# MUX_Block.net
KiCad netlist of a schematic drawn in Altium Designer
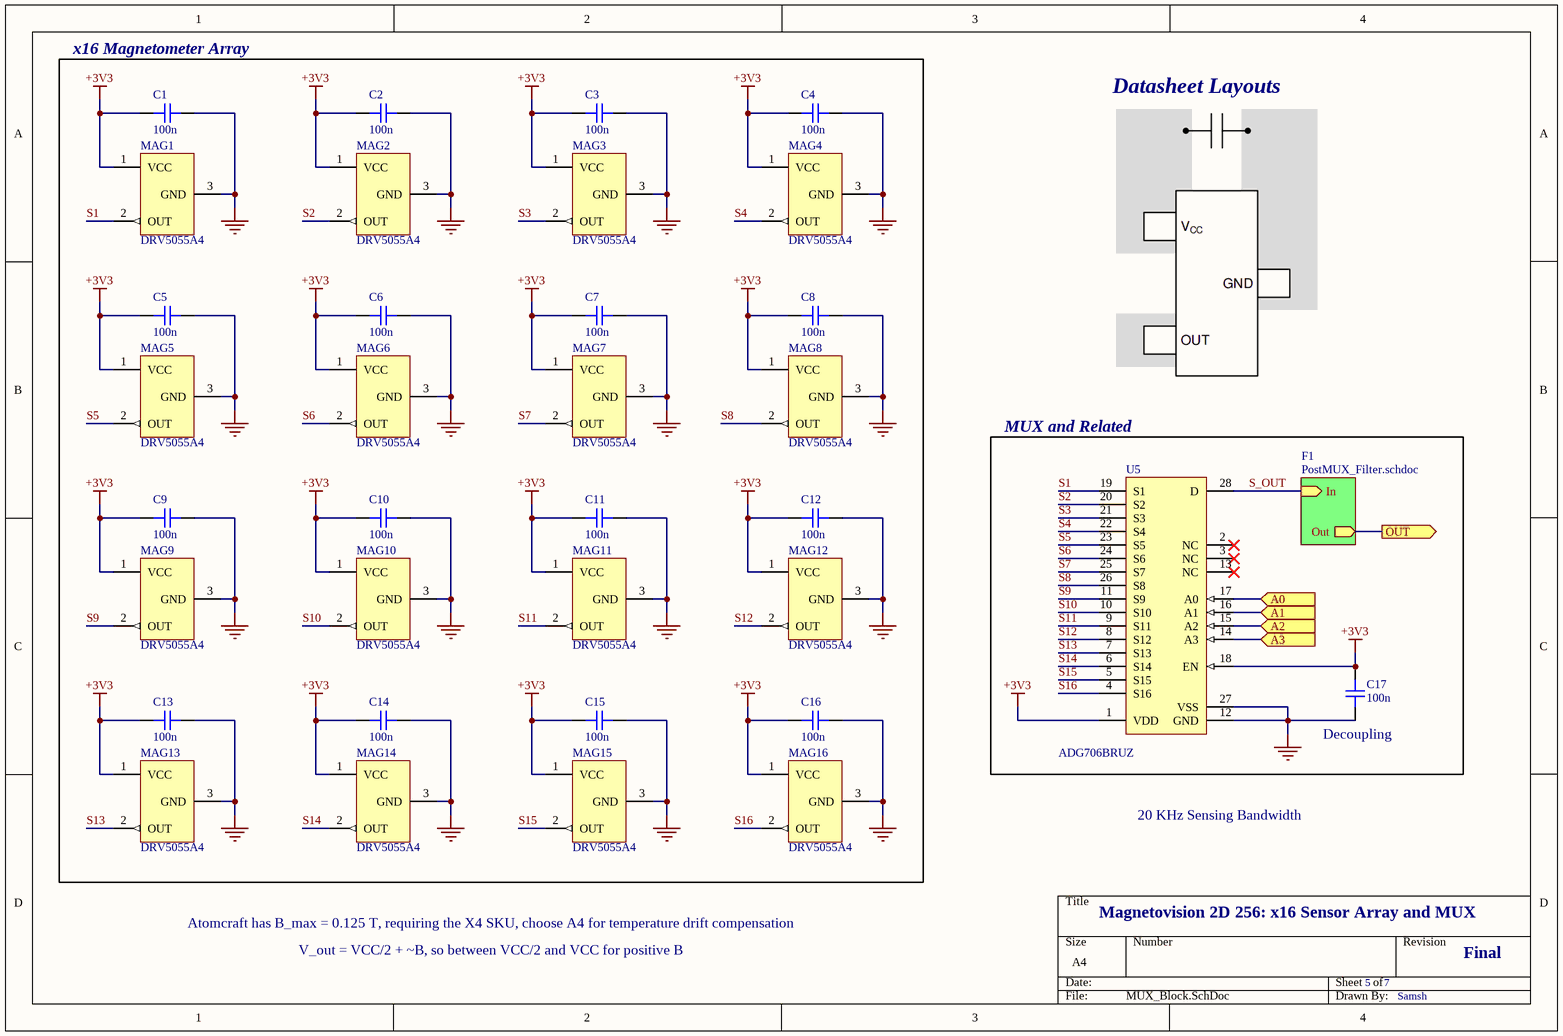
[diagram p0: MUX_Block.SchDoc]

(export (version "E")
  (design (tool "Eeschema 10.0.6"))
  (components
    (comp (ref "C1")
      (value "100n")
      (footprint "CAP_0603")
      (description "Capacitor SMD 0603")
      (fields (field (name "SOURCE") "Schematic-Lib-PhilsLab.SchLib"))
      (libsource (lib "Samsh Nanoelectronics") (part "CAP_EL_NP_5MM"))
    )
    (comp (ref "C2")
      (value "100n")
      (footprint "CAP_0603")
      (description "Capacitor SMD 0603")
      (fields (field (name "SOURCE") "Schematic-Lib-PhilsLab.SchLib"))
      (libsource (lib "Samsh Nanoelectronics") (part "CAP_EL_NP_5MM"))
    )
    (comp (ref "C3")
      (value "100n")
      (footprint "CAP_0603")
      (description "Capacitor SMD 0603")
      (fields (field (name "SOURCE") "Schematic-Lib-PhilsLab.SchLib"))
      (libsource (lib "Samsh Nanoelectronics") (part "CAP_EL_NP_5MM"))
    )
    (comp (ref "C4")
      (value "100n")
      (footprint "CAP_0603")
      (description "Capacitor SMD 0603")
      (fields (field (name "SOURCE") "Schematic-Lib-PhilsLab.SchLib"))
      (libsource (lib "Samsh Nanoelectronics") (part "CAP_EL_NP_5MM"))
    )
    (comp (ref "C5")
      (value "100n")
      (footprint "CAP_0603")
      (description "Capacitor SMD 0603")
      (fields (field (name "SOURCE") "Schematic-Lib-PhilsLab.SchLib"))
      (libsource (lib "Samsh Nanoelectronics") (part "CAP_EL_NP_5MM"))
    )
    (comp (ref "C6")
      (value "100n")
      (footprint "CAP_0603")
      (description "Capacitor SMD 0603")
      (fields (field (name "SOURCE") "Schematic-Lib-PhilsLab.SchLib"))
      (libsource (lib "Samsh Nanoelectronics") (part "CAP_EL_NP_5MM"))
    )
    (comp (ref "C7")
      (value "100n")
      (footprint "CAP_0603")
      (description "Capacitor SMD 0603")
      (fields (field (name "SOURCE") "Schematic-Lib-PhilsLab.SchLib"))
      (libsource (lib "Samsh Nanoelectronics") (part "CAP_EL_NP_5MM"))
    )
    (comp (ref "C8")
      (value "100n")
      (footprint "CAP_0603")
      (description "Capacitor SMD 0603")
      (fields (field (name "SOURCE") "Schematic-Lib-PhilsLab.SchLib"))
      (libsource (lib "Samsh Nanoelectronics") (part "CAP_EL_NP_5MM"))
    )
    (comp (ref "C9")
      (value "100n")
      (footprint "CAP_0603")
      (description "Capacitor SMD 0603")
      (fields (field (name "SOURCE") "Schematic-Lib-PhilsLab.SchLib"))
      (libsource (lib "Samsh Nanoelectronics") (part "CAP_EL_NP_5MM"))
    )
    (comp (ref "C10")
      (value "100n")
      (footprint "CAP_0603")
      (description "Capacitor SMD 0603")
      (fields (field (name "SOURCE") "Schematic-Lib-PhilsLab.SchLib"))
      (libsource (lib "Samsh Nanoelectronics") (part "CAP_EL_NP_5MM"))
    )
    (comp (ref "C11")
      (value "100n")
      (footprint "CAP_0603")
      (description "Capacitor SMD 0603")
      (fields (field (name "SOURCE") "Schematic-Lib-PhilsLab.SchLib"))
      (libsource (lib "Samsh Nanoelectronics") (part "CAP_EL_NP_5MM"))
    )
    (comp (ref "C12")
      (value "100n")
      (footprint "CAP_0603")
      (description "Capacitor SMD 0603")
      (fields (field (name "SOURCE") "Schematic-Lib-PhilsLab.SchLib"))
      (libsource (lib "Samsh Nanoelectronics") (part "CAP_EL_NP_5MM"))
    )
    (comp (ref "C13")
      (value "100n")
      (footprint "CAP_0603")
      (description "Capacitor SMD 0603")
      (fields (field (name "SOURCE") "Schematic-Lib-PhilsLab.SchLib"))
      (libsource (lib "Samsh Nanoelectronics") (part "CAP_EL_NP_5MM"))
    )
    (comp (ref "C14")
      (value "100n")
      (footprint "CAP_0603")
      (description "Capacitor SMD 0603")
      (fields (field (name "SOURCE") "Schematic-Lib-PhilsLab.SchLib"))
      (libsource (lib "Samsh Nanoelectronics") (part "CAP_EL_NP_5MM"))
    )
    (comp (ref "C15")
      (value "100n")
      (footprint "CAP_0603")
      (description "Capacitor SMD 0603")
      (fields (field (name "SOURCE") "Schematic-Lib-PhilsLab.SchLib"))
      (libsource (lib "Samsh Nanoelectronics") (part "CAP_EL_NP_5MM"))
    )
    (comp (ref "C16")
      (value "100n")
      (footprint "CAP_0603")
      (description "Capacitor SMD 0603")
      (fields (field (name "SOURCE") "Schematic-Lib-PhilsLab.SchLib"))
      (libsource (lib "Samsh Nanoelectronics") (part "CAP_EL_NP_5MM"))
    )
    (comp (ref "C17")
      (value "100n")
      (footprint "CAP_0603")
      (description "Capacitor SMD 0603")
      (fields (field (name "SOURCE") "Schematic-Lib-PhilsLab.SchLib"))
      (libsource (lib "Samsh Nanoelectronics") (part "CAP_EL_NP_5MM"))
    )
    (comp (ref "MAG1")
      (value "DRV5055A4")
      (footprint "SOT100P237X112-3N")
      (libsource (lib "Samsh Nanoelectronics") (part "DRV5055A4"))
    )
    (comp (ref "MAG2")
      (value "DRV5055A4")
      (footprint "SOT100P237X112-3N")
      (libsource (lib "Samsh Nanoelectronics") (part "DRV5055A4"))
    )
    (comp (ref "MAG3")
      (value "DRV5055A4")
      (footprint "SOT100P237X112-3N")
      (libsource (lib "Samsh Nanoelectronics") (part "DRV5055A4"))
    )
    (comp (ref "MAG4")
      (value "DRV5055A4")
      (footprint "SOT100P237X112-3N")
      (libsource (lib "Samsh Nanoelectronics") (part "DRV5055A4"))
    )
    (comp (ref "MAG5")
      (value "DRV5055A4")
      (footprint "SOT100P237X112-3N")
      (libsource (lib "Samsh Nanoelectronics") (part "DRV5055A4"))
    )
    (comp (ref "MAG6")
      (value "DRV5055A4")
      (footprint "SOT100P237X112-3N")
      (libsource (lib "Samsh Nanoelectronics") (part "DRV5055A4"))
    )
    (comp (ref "MAG7")
      (value "DRV5055A4")
      (footprint "SOT100P237X112-3N")
      (libsource (lib "Samsh Nanoelectronics") (part "DRV5055A4"))
    )
    (comp (ref "MAG8")
      (value "DRV5055A4")
      (footprint "SOT100P237X112-3N")
      (libsource (lib "Samsh Nanoelectronics") (part "DRV5055A4"))
    )
    (comp (ref "MAG9")
      (value "DRV5055A4")
      (footprint "SOT100P237X112-3N")
      (libsource (lib "Samsh Nanoelectronics") (part "DRV5055A4"))
    )
    (comp (ref "MAG10")
      (value "DRV5055A4")
      (footprint "SOT100P237X112-3N")
      (libsource (lib "Samsh Nanoelectronics") (part "DRV5055A4"))
    )
    (comp (ref "MAG11")
      (value "DRV5055A4")
      (footprint "SOT100P237X112-3N")
      (libsource (lib "Samsh Nanoelectronics") (part "DRV5055A4"))
    )
    (comp (ref "MAG12")
      (value "DRV5055A4")
      (footprint "SOT100P237X112-3N")
      (libsource (lib "Samsh Nanoelectronics") (part "DRV5055A4"))
    )
    (comp (ref "MAG13")
      (value "DRV5055A4")
      (footprint "SOT100P237X112-3N")
      (libsource (lib "Samsh Nanoelectronics") (part "DRV5055A4"))
    )
    (comp (ref "MAG14")
      (value "DRV5055A4")
      (footprint "SOT100P237X112-3N")
      (libsource (lib "Samsh Nanoelectronics") (part "DRV5055A4"))
    )
    (comp (ref "MAG15")
      (value "DRV5055A4")
      (footprint "SOT100P237X112-3N")
      (libsource (lib "Samsh Nanoelectronics") (part "DRV5055A4"))
    )
    (comp (ref "MAG16")
      (value "DRV5055A4")
      (footprint "SOT100P237X112-3N")
      (libsource (lib "Samsh Nanoelectronics") (part "DRV5055A4"))
    )
    (comp (ref "U5")
      (value "ADG706BRUZ")
      (footprint "ADI-RU-28_M")
      (fields (field (name "MANUFACTURER") "Analog Devices") (field (name "PARTNUMBER") "ADG706BRUZ-REEL7"))
      (libsource (lib "Altium Content Vault") (part "ADI-ADG706-RU-28"))
    )
  )
  (nets
    (net (code "1") (name "+3V3") (class "Default")
      (node (ref "C1") (pin "1") (pinfunction "1_1") (pintype "passive"))
      (node (ref "C10") (pin "1") (pinfunction "1_1") (pintype "passive"))
      (node (ref "C11") (pin "1") (pinfunction "1_1") (pintype "passive"))
      (node (ref "C12") (pin "1") (pinfunction "1_1") (pintype "passive"))
      (node (ref "C13") (pin "1") (pinfunction "1_1") (pintype "passive"))
      (node (ref "C14") (pin "1") (pinfunction "1_1") (pintype "passive"))
      (node (ref "C15") (pin "1") (pinfunction "1_1") (pintype "passive"))
      (node (ref "C16") (pin "1") (pinfunction "1_1") (pintype "passive"))
      (node (ref "C17") (pin "2") (pinfunction "2_2") (pintype "passive"))
      (node (ref "C2") (pin "1") (pinfunction "1_1") (pintype "passive"))
      (node (ref "C3") (pin "1") (pinfunction "1_1") (pintype "passive"))
      (node (ref "C4") (pin "1") (pinfunction "1_1") (pintype "passive"))
      (node (ref "C5") (pin "1") (pinfunction "1_1") (pintype "passive"))
      (node (ref "C6") (pin "1") (pinfunction "1_1") (pintype "passive"))
      (node (ref "C7") (pin "1") (pinfunction "1_1") (pintype "passive"))
      (node (ref "C8") (pin "1") (pinfunction "1_1") (pintype "passive"))
      (node (ref "C9") (pin "1") (pinfunction "1_1") (pintype "passive"))
      (node (ref "MAG1") (pin "1") (pinfunction "VCC_1") (pintype "power_in"))
      (node (ref "MAG10") (pin "1") (pinfunction "VCC_1") (pintype "power_in"))
      (node (ref "MAG11") (pin "1") (pinfunction "VCC_1") (pintype "power_in"))
      (node (ref "MAG12") (pin "1") (pinfunction "VCC_1") (pintype "power_in"))
      (node (ref "MAG13") (pin "1") (pinfunction "VCC_1") (pintype "power_in"))
      (node (ref "MAG14") (pin "1") (pinfunction "VCC_1") (pintype "power_in"))
      (node (ref "MAG15") (pin "1") (pinfunction "VCC_1") (pintype "power_in"))
      (node (ref "MAG16") (pin "1") (pinfunction "VCC_1") (pintype "power_in"))
      (node (ref "MAG2") (pin "1") (pinfunction "VCC_1") (pintype "power_in"))
      (node (ref "MAG3") (pin "1") (pinfunction "VCC_1") (pintype "power_in"))
      (node (ref "MAG4") (pin "1") (pinfunction "VCC_1") (pintype "power_in"))
      (node (ref "MAG5") (pin "1") (pinfunction "VCC_1") (pintype "power_in"))
      (node (ref "MAG6") (pin "1") (pinfunction "VCC_1") (pintype "power_in"))
      (node (ref "MAG7") (pin "1") (pinfunction "VCC_1") (pintype "power_in"))
      (node (ref "MAG8") (pin "1") (pinfunction "VCC_1") (pintype "power_in"))
      (node (ref "MAG9") (pin "1") (pinfunction "VCC_1") (pintype "power_in"))
      (node (ref "U5") (pin "1") (pinfunction "VDD_1") (pintype "power_in"))
      (node (ref "U5") (pin "18") (pinfunction "EN_18") (pintype "input"))
    )
    (net (code "2") (name "/A0") (class "Default")
      (node (ref "U5") (pin "17") (pinfunction "A0_17") (pintype "input"))
    )
    (net (code "3") (name "/A1") (class "Default")
      (node (ref "U5") (pin "16") (pinfunction "A1_16") (pintype "input"))
    )
    (net (code "4") (name "/A2") (class "Default")
      (node (ref "U5") (pin "15") (pinfunction "A2_15") (pintype "input"))
    )
    (net (code "5") (name "/A3") (class "Default")
      (node (ref "U5") (pin "14") (pinfunction "A3_14") (pintype "input"))
    )
    (net (code "7") (name "/S1") (class "Default")
      (node (ref "MAG1") (pin "2") (pinfunction "OUT_2") (pintype "output"))
      (node (ref "U5") (pin "19") (pinfunction "S1_19") (pintype "passive"))
    )
    (net (code "8") (name "/S2") (class "Default")
      (node (ref "MAG2") (pin "2") (pinfunction "OUT_2") (pintype "output"))
      (node (ref "U5") (pin "20") (pinfunction "S2_20") (pintype "passive"))
    )
    (net (code "9") (name "/S3") (class "Default")
      (node (ref "MAG3") (pin "2") (pinfunction "OUT_2") (pintype "output"))
      (node (ref "U5") (pin "21") (pinfunction "S3_21") (pintype "passive"))
    )
    (net (code "10") (name "/S4") (class "Default")
      (node (ref "MAG4") (pin "2") (pinfunction "OUT_2") (pintype "output"))
      (node (ref "U5") (pin "22") (pinfunction "S4_22") (pintype "passive"))
    )
    (net (code "11") (name "/S5") (class "Default")
      (node (ref "MAG5") (pin "2") (pinfunction "OUT_2") (pintype "output"))
      (node (ref "U5") (pin "23") (pinfunction "S5_23") (pintype "passive"))
    )
    (net (code "12") (name "/S6") (class "Default")
      (node (ref "MAG6") (pin "2") (pinfunction "OUT_2") (pintype "output"))
      (node (ref "U5") (pin "24") (pinfunction "S6_24") (pintype "passive"))
    )
    (net (code "13") (name "/S7") (class "Default")
      (node (ref "MAG7") (pin "2") (pinfunction "OUT_2") (pintype "output"))
      (node (ref "U5") (pin "25") (pinfunction "S7_25") (pintype "passive"))
    )
    (net (code "14") (name "/S8") (class "Default")
      (node (ref "MAG8") (pin "2") (pinfunction "OUT_2") (pintype "output"))
      (node (ref "U5") (pin "26") (pinfunction "S8_26") (pintype "passive"))
    )
    (net (code "15") (name "/S9") (class "Default")
      (node (ref "MAG9") (pin "2") (pinfunction "OUT_2") (pintype "output"))
      (node (ref "U5") (pin "11") (pinfunction "S9_11") (pintype "passive"))
    )
    (net (code "16") (name "/S10") (class "Default")
      (node (ref "MAG10") (pin "2") (pinfunction "OUT_2") (pintype "output"))
      (node (ref "U5") (pin "10") (pinfunction "S10_10") (pintype "passive"))
    )
    (net (code "17") (name "/S11") (class "Default")
      (node (ref "MAG11") (pin "2") (pinfunction "OUT_2") (pintype "output"))
      (node (ref "U5") (pin "9") (pinfunction "S11_9") (pintype "passive"))
    )
    (net (code "18") (name "/S12") (class "Default")
      (node (ref "MAG12") (pin "2") (pinfunction "OUT_2") (pintype "output"))
      (node (ref "U5") (pin "8") (pinfunction "S12_8") (pintype "passive"))
    )
    (net (code "19") (name "/S13") (class "Default")
      (node (ref "MAG13") (pin "2") (pinfunction "OUT_2") (pintype "output"))
      (node (ref "U5") (pin "7") (pinfunction "S13_7") (pintype "passive"))
    )
    (net (code "20") (name "/S14") (class "Default")
      (node (ref "MAG14") (pin "2") (pinfunction "OUT_2") (pintype "output"))
      (node (ref "U5") (pin "6") (pinfunction "S14_6") (pintype "passive"))
    )
    (net (code "21") (name "/S15") (class "Default")
      (node (ref "MAG15") (pin "2") (pinfunction "OUT_2") (pintype "output"))
      (node (ref "U5") (pin "5") (pinfunction "S15_5") (pintype "passive"))
    )
    (net (code "22") (name "/S16") (class "Default")
      (node (ref "MAG16") (pin "2") (pinfunction "OUT_2") (pintype "output"))
      (node (ref "U5") (pin "4") (pinfunction "S16_4") (pintype "passive"))
    )
    (net (code "23") (name "/S_OUT") (class "Default")
      (node (ref "U5") (pin "28") (pinfunction "D_28") (pintype "passive"))
    )
    (net (code "24") (name "GND") (class "Default")
      (node (ref "C1") (pin "2") (pinfunction "2_2") (pintype "passive"))
      (node (ref "C10") (pin "2") (pinfunction "2_2") (pintype "passive"))
      (node (ref "C11") (pin "2") (pinfunction "2_2") (pintype "passive"))
      (node (ref "C12") (pin "2") (pinfunction "2_2") (pintype "passive"))
      (node (ref "C13") (pin "2") (pinfunction "2_2") (pintype "passive"))
      (node (ref "C14") (pin "2") (pinfunction "2_2") (pintype "passive"))
      (node (ref "C15") (pin "2") (pinfunction "2_2") (pintype "passive"))
      (node (ref "C16") (pin "2") (pinfunction "2_2") (pintype "passive"))
      (node (ref "C17") (pin "1") (pinfunction "1_1") (pintype "passive"))
      (node (ref "C2") (pin "2") (pinfunction "2_2") (pintype "passive"))
      (node (ref "C3") (pin "2") (pinfunction "2_2") (pintype "passive"))
      (node (ref "C4") (pin "2") (pinfunction "2_2") (pintype "passive"))
      (node (ref "C5") (pin "2") (pinfunction "2_2") (pintype "passive"))
      (node (ref "C6") (pin "2") (pinfunction "2_2") (pintype "passive"))
      (node (ref "C7") (pin "2") (pinfunction "2_2") (pintype "passive"))
      (node (ref "C8") (pin "2") (pinfunction "2_2") (pintype "passive"))
      (node (ref "C9") (pin "2") (pinfunction "2_2") (pintype "passive"))
      (node (ref "MAG1") (pin "3") (pinfunction "GND_3") (pintype "passive"))
      (node (ref "MAG10") (pin "3") (pinfunction "GND_3") (pintype "passive"))
      (node (ref "MAG11") (pin "3") (pinfunction "GND_3") (pintype "passive"))
      (node (ref "MAG12") (pin "3") (pinfunction "GND_3") (pintype "passive"))
      (node (ref "MAG13") (pin "3") (pinfunction "GND_3") (pintype "passive"))
      (node (ref "MAG14") (pin "3") (pinfunction "GND_3") (pintype "passive"))
      (node (ref "MAG15") (pin "3") (pinfunction "GND_3") (pintype "passive"))
      (node (ref "MAG16") (pin "3") (pinfunction "GND_3") (pintype "passive"))
      (node (ref "MAG2") (pin "3") (pinfunction "GND_3") (pintype "passive"))
      (node (ref "MAG3") (pin "3") (pinfunction "GND_3") (pintype "passive"))
      (node (ref "MAG4") (pin "3") (pinfunction "GND_3") (pintype "passive"))
      (node (ref "MAG5") (pin "3") (pinfunction "GND_3") (pintype "passive"))
      (node (ref "MAG6") (pin "3") (pinfunction "GND_3") (pintype "passive"))
      (node (ref "MAG7") (pin "3") (pinfunction "GND_3") (pintype "passive"))
      (node (ref "MAG8") (pin "3") (pinfunction "GND_3") (pintype "passive"))
      (node (ref "MAG9") (pin "3") (pinfunction "GND_3") (pintype "passive"))
      (node (ref "U5") (pin "12") (pinfunction "GND_12") (pintype "power_in"))
      (node (ref "U5") (pin "27") (pinfunction "VSS_27") (pintype "power_in"))
    )
    (net (code "25") (name "unconnected-(U5-NC-Pad2)") (class "Default")
      (node (ref "U5") (pin "2") (pinfunction "NC_2") (pintype "passive+no_connect"))
    )
    (net (code "26") (name "unconnected-(U5-NC-Pad3)") (class "Default")
      (node (ref "U5") (pin "3") (pinfunction "NC_3") (pintype "passive+no_connect"))
    )
    (net (code "27") (name "unconnected-(U5-NC-Pad13)") (class "Default")
      (node (ref "U5") (pin "13") (pinfunction "NC_13") (pintype "passive+no_connect"))
    )
  )
)
